# 08_User_IO.net
KiCad netlist of a schematic drawn in Altium Designer
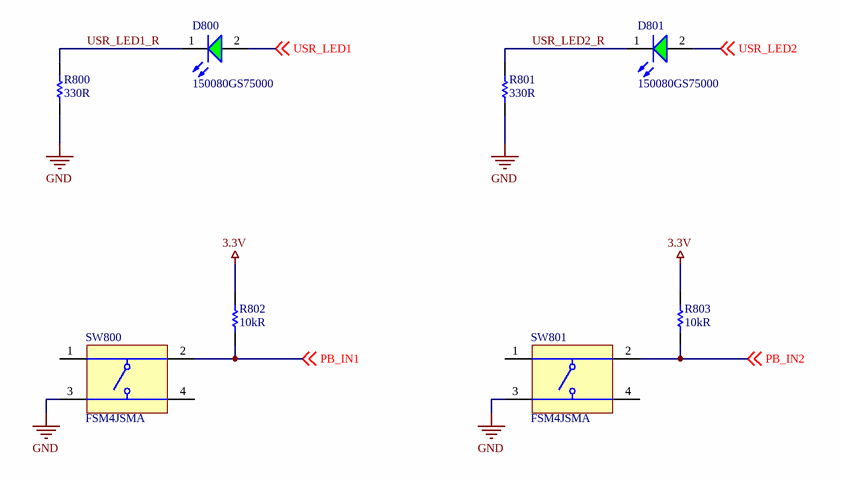
[diagram p0: 08_User_IO.SchDoc]

(export (version "E")
  (design (tool "Eeschema 10.0.6"))
  (components
    (comp (ref "D800")
      (value "150080GS75000")
      (footprint "WL-SMCW_0805_150080xx75000")
      (libsource (lib "Altium Content Vault") (part "LED_Green_2A-1K"))
    )
    (comp (ref "D801")
      (value "150080GS75000")
      (footprint "WL-SMCW_0805_150080xx75000")
      (libsource (lib "Altium Content Vault") (part "LED_Green_2A-1K"))
    )
    (comp (ref "R800")
      (value "330R")
      (footprint "RESC2013X60X40LL20T25")
      (fields (field (name "MANUFACTURER") "Panasonic") (field (name "PART NUMBER") "ERA6AEB331V"))
      (libsource (lib "Altium Content Vault") (part "RES"))
    )
    (comp (ref "R801")
      (value "330R")
      (footprint "RESC2013X60X40LL20T25")
      (fields (field (name "MANUFACTURER") "Panasonic") (field (name "PART NUMBER") "ERA6AEB331V"))
      (libsource (lib "Altium Content Vault") (part "RES"))
    )
    (comp (ref "R802")
      (value "10kR")
      (footprint "RESC2013X70X40ML20T20")
      (fields (field (name "MANUFACTURER") "Panasonic") (field (name "PART NUMBER") "ERJ-6ENF1002V"))
      (libsource (lib "Altium Content Vault") (part "RES"))
    )
    (comp (ref "R803")
      (value "10kR")
      (footprint "RESC2013X70X40ML20T20")
      (fields (field (name "MANUFACTURER") "Panasonic") (field (name "PART NUMBER") "ERJ-6ENF1002V"))
      (libsource (lib "Altium Content Vault") (part "RES"))
    )
    (comp (ref "SW800")
      (value "FSM4JSMA")
      (footprint "TECO-FSM4JSMA_V")
      (description "Swicth, SPST, 24 V, -35 to 85 degC, 4-Pin SMD, RoHS, Tape and Reel")
      (fields (field (name "MANUFACTURER") "TE Connectivity"))
      (libsource (lib "Altium Content Vault") (part "SW-SPST-4_A"))
    )
    (comp (ref "SW801")
      (value "FSM4JSMA")
      (footprint "TECO-FSM4JSMA_V")
      (description "Swicth, SPST, 24 V, -35 to 85 degC, 4-Pin SMD, RoHS, Tape and Reel")
      (fields (field (name "MANUFACTURER") "TE Connectivity"))
      (libsource (lib "Altium Content Vault") (part "SW-SPST-4_A"))
    )
  )
  (nets
    (net (code "1") (name "/USR_LED1_R") (class "Default")
      (node (ref "D800") (pin "1") (pinfunction "K_1") (pintype "passive"))
      (node (ref "R800") (pin "1") (pinfunction "1_1") (pintype "passive"))
    )
    (net (code "2") (name "/USR_LED2_R") (class "Default")
      (node (ref "D801") (pin "1") (pinfunction "K_1") (pintype "passive"))
      (node (ref "R801") (pin "1") (pinfunction "1_1") (pintype "passive"))
    )
    (net (code "3") (name "3.3V") (class "Default")
      (node (ref "R802") (pin "2") (pinfunction "2_2") (pintype "passive"))
      (node (ref "R803") (pin "2") (pinfunction "2_2") (pintype "passive"))
    )
    (net (code "4") (name "GND") (class "Default")
      (node (ref "R800") (pin "2") (pinfunction "2_2") (pintype "passive"))
      (node (ref "R801") (pin "2") (pinfunction "2_2") (pintype "passive"))
      (node (ref "SW800") (pin "3") (pinfunction "3_3") (pintype "passive"))
      (node (ref "SW801") (pin "3") (pinfunction "3_3") (pintype "passive"))
    )
    (net (code "5") (name "PB_IN1") (class "Default")
      (node (ref "R802") (pin "1") (pinfunction "1_1") (pintype "passive"))
      (node (ref "SW800") (pin "2") (pinfunction "2_2") (pintype "passive"))
    )
    (net (code "6") (name "PB_IN2") (class "Default")
      (node (ref "R803") (pin "1") (pinfunction "1_1") (pintype "passive"))
      (node (ref "SW801") (pin "2") (pinfunction "2_2") (pintype "passive"))
    )
    (net (code "7") (name "USR_LED1") (class "Default")
      (node (ref "D800") (pin "2") (pinfunction "A_2") (pintype "passive"))
    )
    (net (code "8") (name "USR_LED2") (class "Default")
      (node (ref "D801") (pin "2") (pinfunction "A_2") (pintype "passive"))
    )
    (net (code "9") (name "unconnected-(SW800-Pad1)") (class "Default")
      (node (ref "SW800") (pin "1") (pinfunction "1_1") (pintype "passive"))
    )
    (net (code "10") (name "unconnected-(SW800-Pad4)") (class "Default")
      (node (ref "SW800") (pin "4") (pinfunction "4_4") (pintype "passive"))
    )
    (net (code "11") (name "unconnected-(SW801-Pad1)") (class "Default")
      (node (ref "SW801") (pin "1") (pinfunction "1_1") (pintype "passive"))
    )
    (net (code "12") (name "unconnected-(SW801-Pad4)") (class "Default")
      (node (ref "SW801") (pin "4") (pinfunction "4_4") (pintype "passive"))
    )
  )
)
